# Sheet05.net
KiCad netlist of a schematic drawn in Altium Designer
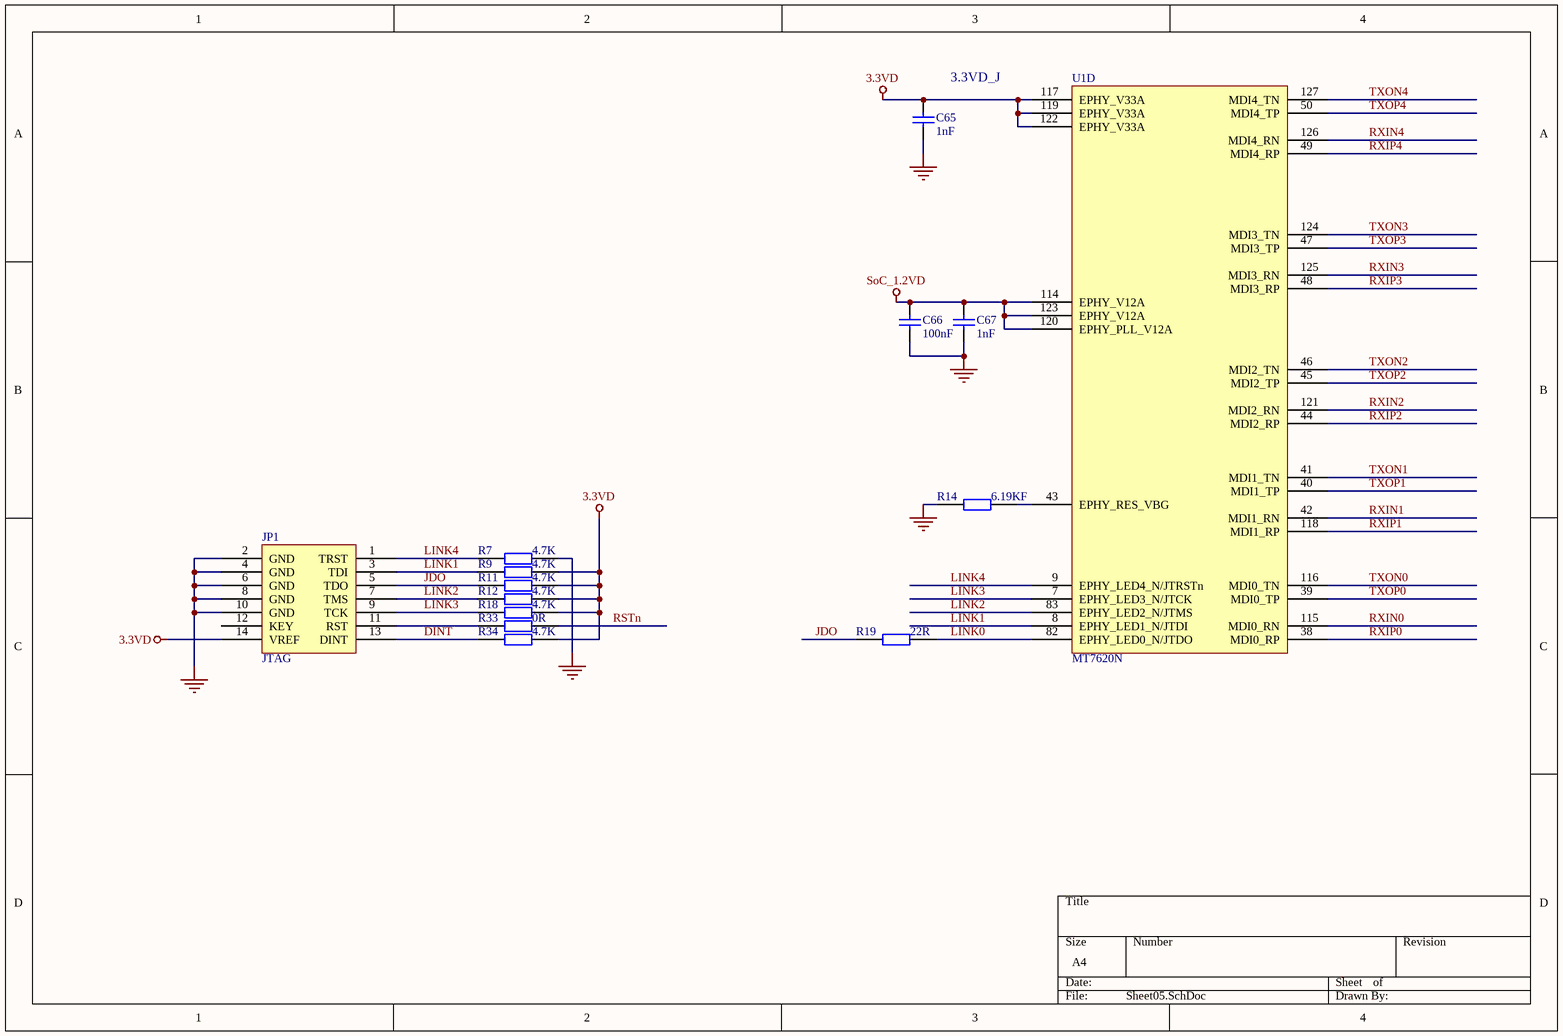
[diagram p0: Sheet05.SchDoc]

(export (version "E")
  (design (tool "Eeschema 10.0.6"))
  (components
    (comp (ref "C65")
      (value "1nF")
      (footprint "R0402")
      (description "2pF, 50V, +/-0.25pF")
      (fields
        (field (name "MANUFACTURER") "Generic Components")
        (field (name "PUBLISHER") "Altium Hobart Technology Centre")
      )
      (libsource (lib "myschlib") (part "Cap Semi"))
    )
    (comp (ref "C66")
      (value "100nF")
      (footprint "R0402")
      (description "2pF, 50V, +/-0.25pF")
      (fields
        (field (name "MANUFACTURER") "Generic Components")
        (field (name "PUBLISHER") "Altium Hobart Technology Centre")
      )
      (libsource (lib "myschlib") (part "Cap Semi"))
    )
    (comp (ref "C67")
      (value "1nF")
      (footprint "R0402")
      (description "2pF, 50V, +/-0.25pF")
      (fields
        (field (name "MANUFACTURER") "Generic Components")
        (field (name "PUBLISHER") "Altium Hobart Technology Centre")
      )
      (libsource (lib "myschlib") (part "Cap Semi"))
    )
    (comp (ref "JP1") (value "JTAG") (footprint "IDC-2X7-2_54-M") (libsource (lib "myschlib") (part "JTAG")))
    (comp (ref "R7") (value "4.7K") (footprint "R0402") (libsource (lib "myschlib") (part "RES")))
    (comp (ref "R9") (value "4.7K") (footprint "R0402") (libsource (lib "myschlib") (part "RES")))
    (comp (ref "R11") (value "4.7K") (footprint "R0402") (libsource (lib "myschlib") (part "RES")))
    (comp (ref "R12") (value "4.7K") (footprint "R0402") (libsource (lib "myschlib") (part "RES")))
    (comp (ref "R14") (value "6.19KF") (footprint "R0402") (libsource (lib "myschlib") (part "RES")))
    (comp (ref "R18") (value "4.7K") (footprint "R0402") (libsource (lib "myschlib") (part "RES")))
    (comp (ref "R19") (value "22R") (footprint "R0402") (libsource (lib "myschlib") (part "RES")))
    (comp (ref "R33") (value "0R") (footprint "R0402") (libsource (lib "myschlib") (part "RES")))
    (comp (ref "R34") (value "4.7K") (footprint "R0402") (libsource (lib "myschlib") (part "RES")))
    (comp (ref "U1") (value "MT7620N") (footprint "QFN-148-RT") (libsource (lib "myschlib") (part "MT7620N")))
  )
  (nets
    (net (code "1") (name "/DINT") (class "Default")
      (node (ref "JP1") (pin "13") (pinfunction "DINT_13") (pintype "passive"))
      (node (ref "R34") (pin "2") (pinfunction "2_2") (pintype "passive"))
    )
    (net (code "2") (name "/JDO") (class "Default")
      (node (ref "JP1") (pin "5") (pinfunction "TDO_5") (pintype "passive"))
      (node (ref "R11") (pin "2") (pinfunction "2_2") (pintype "passive"))
      (node (ref "R19") (pin "2") (pinfunction "2_2") (pintype "passive"))
    )
    (net (code "3") (name "/LINK0") (class "Default")
      (node (ref "R19") (pin "1") (pinfunction "1_1") (pintype "passive"))
      (node (ref "U1") (pin "82") (pinfunction "EPHY_LED0_N/JTDO_82") (pintype "passive"))
    )
    (net (code "4") (name "/LINK1") (class "Default")
      (node (ref "JP1") (pin "3") (pinfunction "TDI_3") (pintype "passive"))
      (node (ref "R9") (pin "2") (pinfunction "2_2") (pintype "passive"))
      (node (ref "U1") (pin "8") (pinfunction "EPHY_LED1_N/JTDI_8") (pintype "passive"))
    )
    (net (code "5") (name "/LINK2") (class "Default")
      (node (ref "JP1") (pin "7") (pinfunction "TMS_7") (pintype "passive"))
      (node (ref "R12") (pin "2") (pinfunction "2_2") (pintype "passive"))
      (node (ref "U1") (pin "83") (pinfunction "EPHY_LED2_N/JTMS_83") (pintype "passive"))
    )
    (net (code "6") (name "/LINK3") (class "Default")
      (node (ref "JP1") (pin "9") (pinfunction "TCK_9") (pintype "passive"))
      (node (ref "R18") (pin "2") (pinfunction "2_2") (pintype "passive"))
      (node (ref "U1") (pin "7") (pinfunction "EPHY_LED3_N/JTCK_7") (pintype "passive"))
    )
    (net (code "7") (name "/LINK4") (class "Default")
      (node (ref "JP1") (pin "1") (pinfunction "TRST_1") (pintype "passive"))
      (node (ref "R7") (pin "2") (pinfunction "2_2") (pintype "passive"))
      (node (ref "U1") (pin "9") (pinfunction "EPHY_LED4_N/JTRSTn_9") (pintype "passive"))
    )
    (net (code "8") (name "/RSTn") (class "Default")
      (node (ref "R33") (pin "1") (pinfunction "1_1") (pintype "passive"))
    )
    (net (code "9") (name "/RXIN0") (class "Default")
      (node (ref "U1") (pin "115") (pinfunction "MDI0_RN_115") (pintype "passive"))
    )
    (net (code "10") (name "/RXIN1") (class "Default")
      (node (ref "U1") (pin "42") (pinfunction "MDI1_RN_42") (pintype "passive"))
    )
    (net (code "11") (name "/RXIN2") (class "Default")
      (node (ref "U1") (pin "121") (pinfunction "MDI2_RN_121") (pintype "passive"))
    )
    (net (code "12") (name "/RXIN3") (class "Default")
      (node (ref "U1") (pin "125") (pinfunction "MDI3_RN_125") (pintype "passive"))
    )
    (net (code "13") (name "/RXIN4") (class "Default")
      (node (ref "U1") (pin "126") (pinfunction "MDI4_RN_126") (pintype "passive"))
    )
    (net (code "14") (name "/RXIP0") (class "Default")
      (node (ref "U1") (pin "38") (pinfunction "MDI0_RP_38") (pintype "passive"))
    )
    (net (code "15") (name "/RXIP1") (class "Default")
      (node (ref "U1") (pin "118") (pinfunction "MDI1_RP_118") (pintype "passive"))
    )
    (net (code "16") (name "/RXIP2") (class "Default")
      (node (ref "U1") (pin "44") (pinfunction "MDI2_RP_44") (pintype "passive"))
    )
    (net (code "17") (name "/RXIP3") (class "Default")
      (node (ref "U1") (pin "48") (pinfunction "MDI3_RP_48") (pintype "passive"))
    )
    (net (code "18") (name "/RXIP4") (class "Default")
      (node (ref "U1") (pin "49") (pinfunction "MDI4_RP_49") (pintype "passive"))
    )
    (net (code "19") (name "/TXON0") (class "Default")
      (node (ref "U1") (pin "116") (pinfunction "MDI0_TN_116") (pintype "passive"))
    )
    (net (code "20") (name "/TXON1") (class "Default")
      (node (ref "U1") (pin "41") (pinfunction "MDI1_TN_41") (pintype "passive"))
    )
    (net (code "21") (name "/TXON2") (class "Default")
      (node (ref "U1") (pin "46") (pinfunction "MDI2_TN_46") (pintype "passive"))
    )
    (net (code "22") (name "/TXON3") (class "Default")
      (node (ref "U1") (pin "124") (pinfunction "MDI3_TN_124") (pintype "passive"))
    )
    (net (code "23") (name "/TXON4") (class "Default")
      (node (ref "U1") (pin "127") (pinfunction "MDI4_TN_127") (pintype "passive"))
    )
    (net (code "24") (name "/TXOP0") (class "Default")
      (node (ref "U1") (pin "39") (pinfunction "MDI0_TP_39") (pintype "passive"))
    )
    (net (code "25") (name "/TXOP1") (class "Default")
      (node (ref "U1") (pin "40") (pinfunction "MDI1_TP_40") (pintype "passive"))
    )
    (net (code "26") (name "/TXOP2") (class "Default")
      (node (ref "U1") (pin "45") (pinfunction "MDI2_TP_45") (pintype "passive"))
    )
    (net (code "27") (name "/TXOP3") (class "Default")
      (node (ref "U1") (pin "47") (pinfunction "MDI3_TP_47") (pintype "passive"))
    )
    (net (code "28") (name "/TXOP4") (class "Default")
      (node (ref "U1") (pin "50") (pinfunction "MDI4_TP_50") (pintype "passive"))
    )
    (net (code "29") (name "3.3VD") (class "Default")
      (node (ref "C65") (pin "1") (pinfunction "1_1") (pintype "passive"))
      (node (ref "JP1") (pin "14") (pinfunction "VREF_14") (pintype "passive"))
      (node (ref "R11") (pin "1") (pinfunction "1_1") (pintype "passive"))
      (node (ref "R12") (pin "1") (pinfunction "1_1") (pintype "passive"))
      (node (ref "R18") (pin "1") (pinfunction "1_1") (pintype "passive"))
      (node (ref "R34") (pin "1") (pinfunction "1_1") (pintype "passive"))
      (node (ref "R9") (pin "1") (pinfunction "1_1") (pintype "passive"))
      (node (ref "U1") (pin "117") (pinfunction "EPHY_V33A_117") (pintype "passive"))
      (node (ref "U1") (pin "119") (pinfunction "EPHY_V33A_119") (pintype "passive"))
      (node (ref "U1") (pin "122") (pinfunction "EPHY_V33A_122") (pintype "passive"))
    )
    (net (code "30") (name "GND") (class "Default")
      (node (ref "C65") (pin "2") (pinfunction "2_2") (pintype "passive"))
      (node (ref "C66") (pin "2") (pinfunction "2_2") (pintype "passive"))
      (node (ref "C67") (pin "2") (pinfunction "2_2") (pintype "passive"))
      (node (ref "JP1") (pin "10") (pinfunction "GND_10") (pintype "passive"))
      (node (ref "JP1") (pin "2") (pinfunction "GND_2") (pintype "passive"))
      (node (ref "JP1") (pin "4") (pinfunction "GND_4") (pintype "passive"))
      (node (ref "JP1") (pin "6") (pinfunction "GND_6") (pintype "passive"))
      (node (ref "JP1") (pin "8") (pinfunction "GND_8") (pintype "passive"))
      (node (ref "R14") (pin "2") (pinfunction "2_2") (pintype "passive"))
      (node (ref "R7") (pin "1") (pinfunction "1_1") (pintype "passive"))
    )
    (net (code "31") (name "Net-(JP1-RST)") (class "Default")
      (node (ref "JP1") (pin "11") (pinfunction "RST_11") (pintype "passive"))
      (node (ref "R33") (pin "2") (pinfunction "2_2") (pintype "passive"))
    )
    (net (code "32") (name "Net-(U1D-EPHY_RES_VBG)") (class "Default")
      (node (ref "R14") (pin "1") (pinfunction "1_1") (pintype "passive"))
      (node (ref "U1") (pin "43") (pinfunction "EPHY_RES_VBG_43") (pintype "passive"))
    )
    (net (code "33") (name "SoC_1.2VD") (class "Default")
      (node (ref "C66") (pin "1") (pinfunction "1_1") (pintype "passive"))
      (node (ref "C67") (pin "1") (pinfunction "1_1") (pintype "passive"))
      (node (ref "U1") (pin "114") (pinfunction "EPHY_V12A_114") (pintype "passive"))
      (node (ref "U1") (pin "120") (pinfunction "EPHY_PLL_V12A_120") (pintype "passive"))
      (node (ref "U1") (pin "123") (pinfunction "EPHY_V12A_123") (pintype "passive"))
    )
    (net (code "34") (name "unconnected-(JP1-KEY-Pad12)") (class "Default")
      (node (ref "JP1") (pin "12") (pinfunction "KEY_12") (pintype "passive"))
    )
  )
)
